# LurkerNanov12.net
KiCad netlist of a schematic drawn in EAGLE
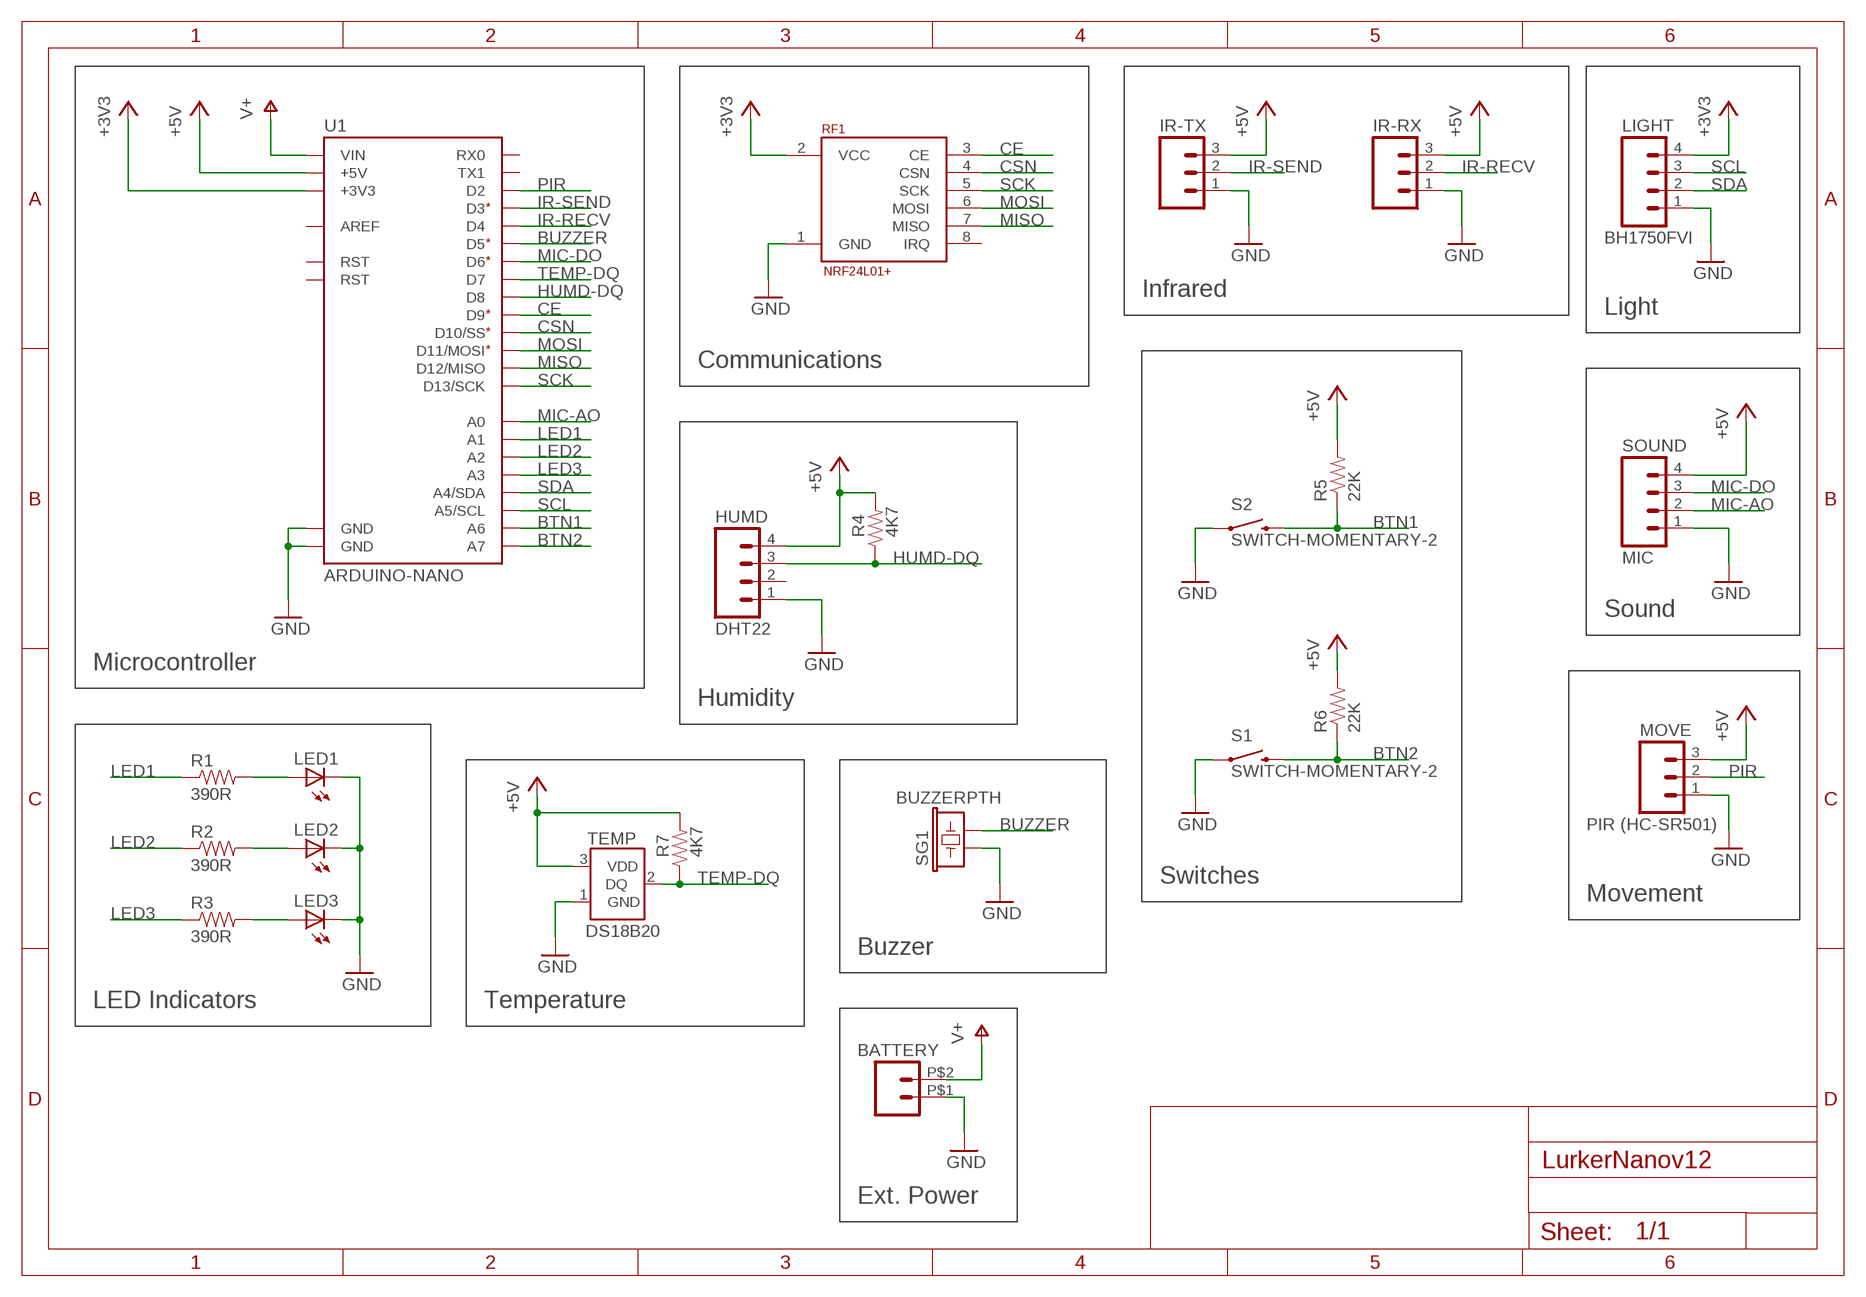
[diagram p0: schematic, sheet 1, part 1 of 2]
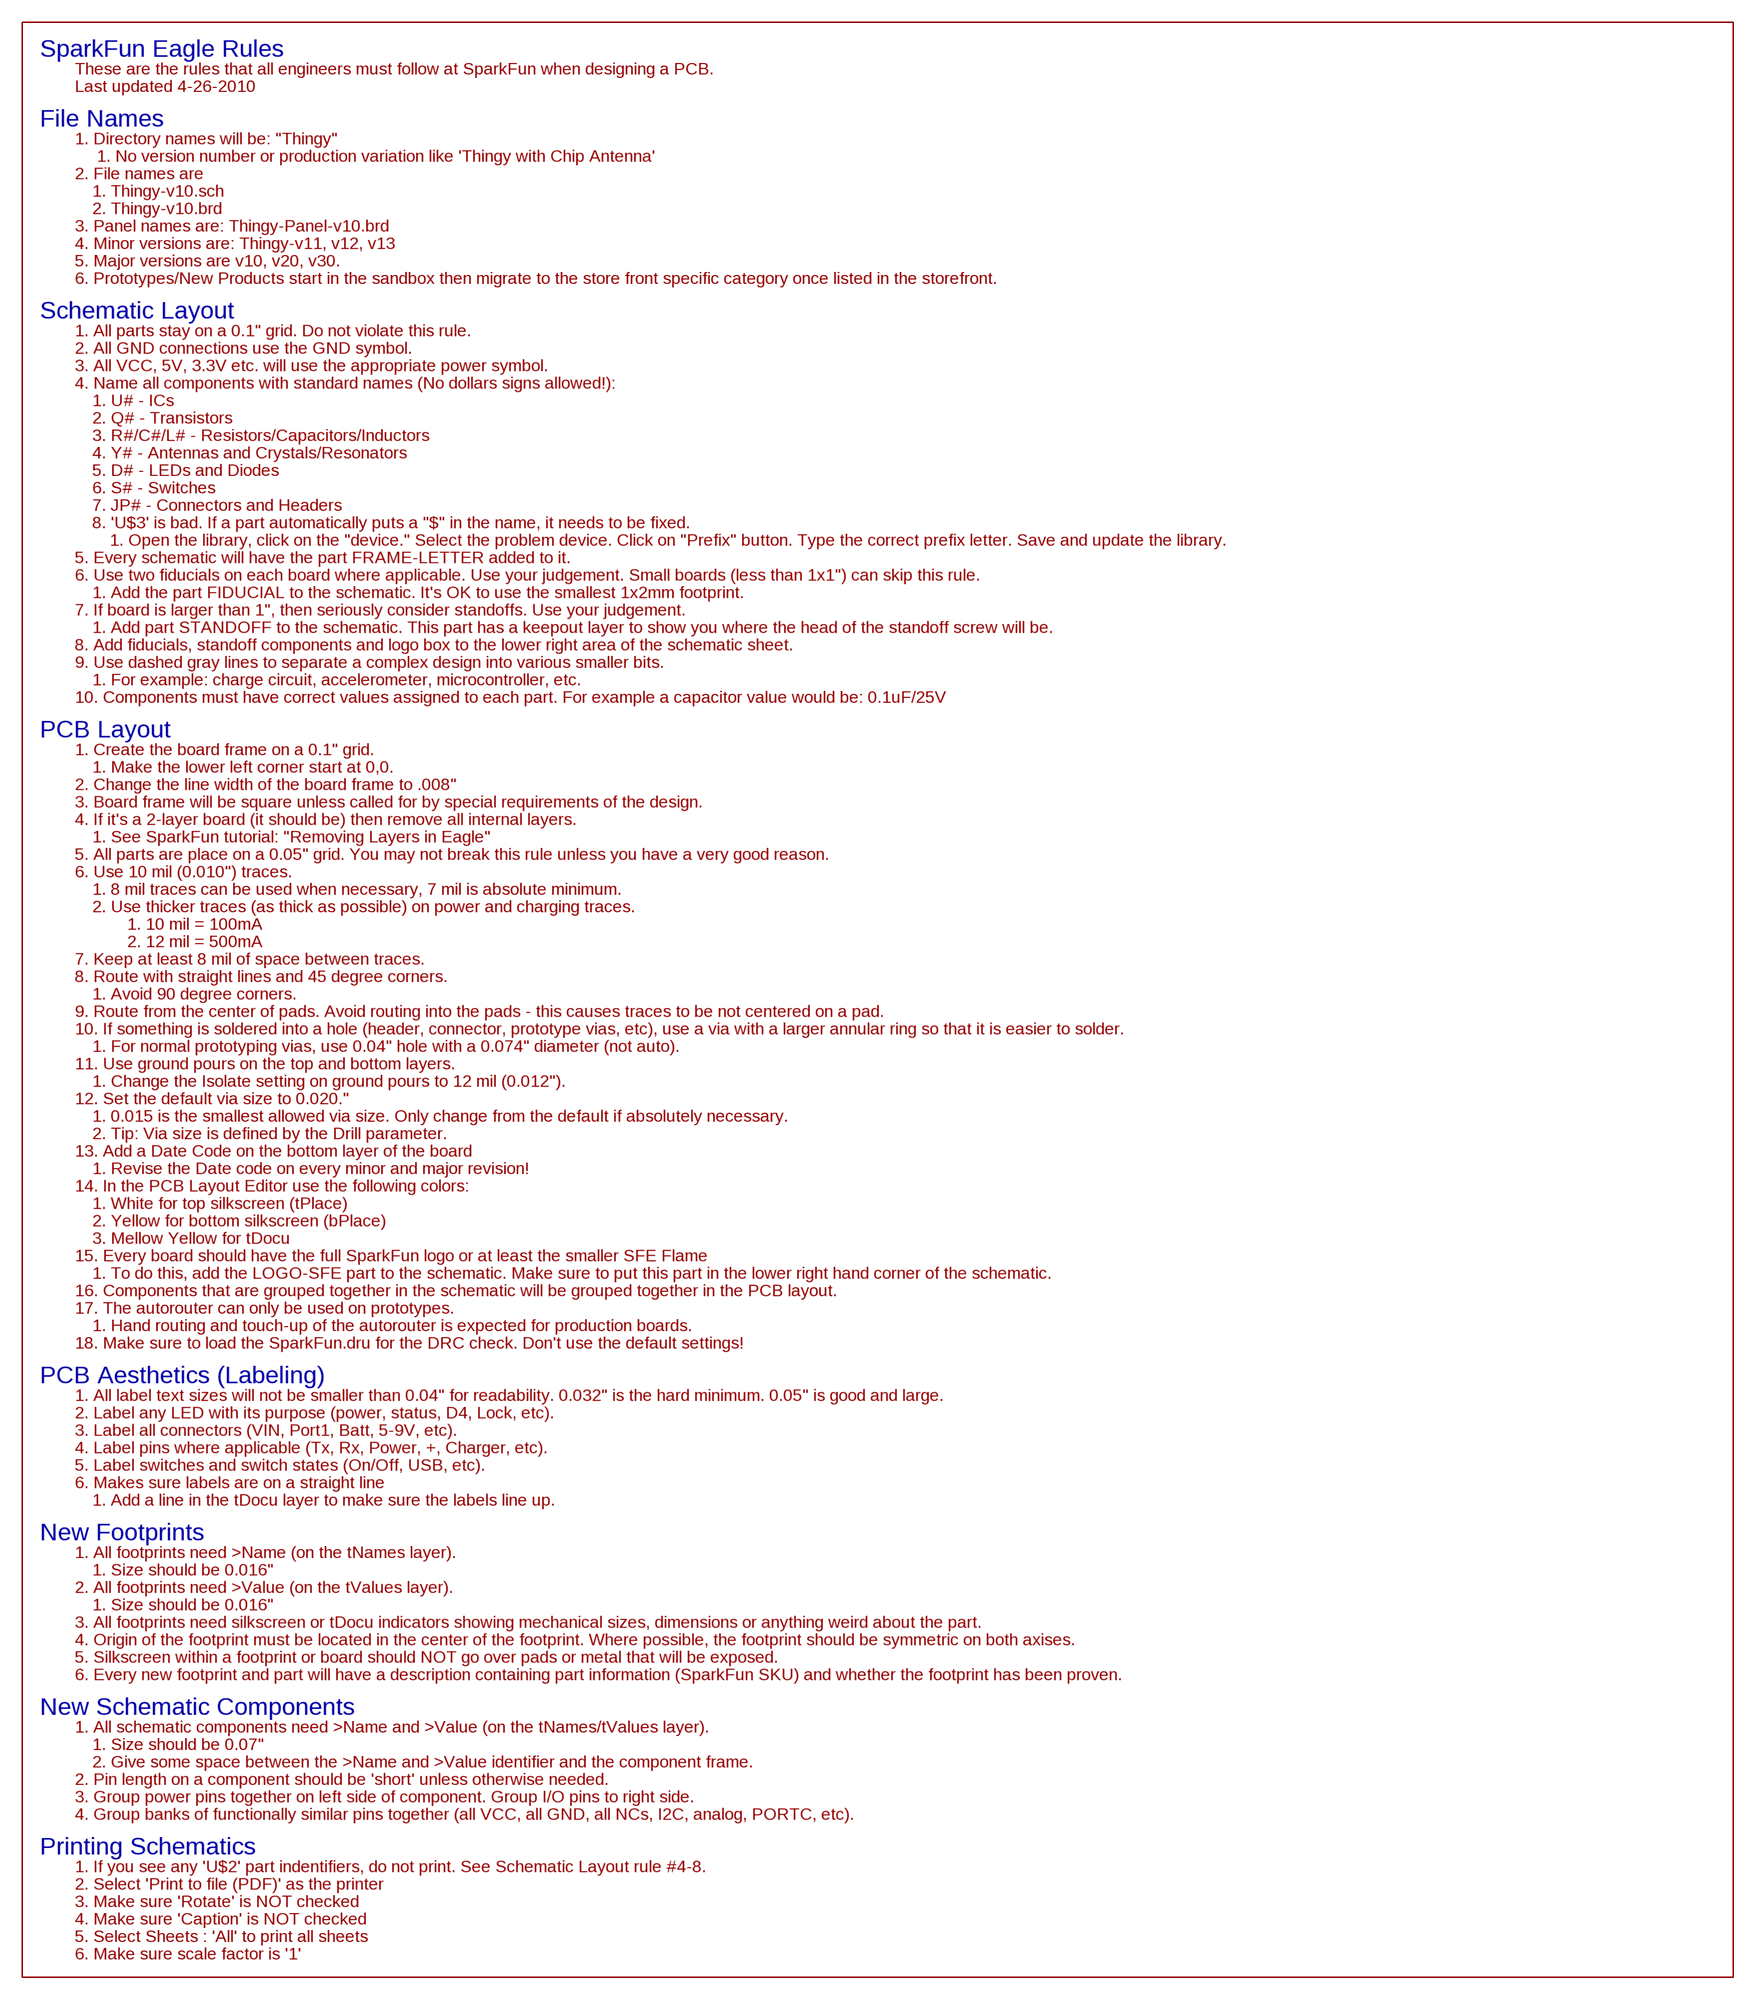
[diagram p1: schematic, sheet 1, part 2 of 2]

(export (version "E")
  (design (tool "Eeschema 10.0.6"))
  (components
    (comp (ref "BATTERY")
      (value "M02PTH2")
      (footprint "eagle-import:1X02_BIG")
      (libsource (lib "eagle-import") (part "M02PTH2"))
    )
    (comp (ref "HUMD")
      (value "DHT22")
      (footprint "eagle-import:1X04")
      (libsource (lib "eagle-import") (part "M04PTH"))
    )
    (comp (ref "IR-RX")
      (value "M03PTH")
      (footprint "eagle-import:1X03")
      (libsource (lib "eagle-import") (part "M03PTH"))
    )
    (comp (ref "IR-TX")
      (value "M03PTH")
      (footprint "eagle-import:1X03")
      (libsource (lib "eagle-import") (part "M03PTH"))
    )
    (comp (ref "LED1")
      (value "LED1206")
      (footprint "eagle-import:LED-1206")
      (libsource (lib "eagle-import") (part "LED1206"))
    )
    (comp (ref "LED2")
      (value "LED1206")
      (footprint "eagle-import:LED-1206")
      (libsource (lib "eagle-import") (part "LED1206"))
    )
    (comp (ref "LED3")
      (value "LED1206")
      (footprint "eagle-import:LED-1206")
      (libsource (lib "eagle-import") (part "LED1206"))
    )
    (comp (ref "LIGHT")
      (value "BH1750FVI")
      (footprint "eagle-import:1X04")
      (libsource (lib "eagle-import") (part "M04PTH"))
    )
    (comp (ref "MOVE")
      (value "PIR (HC-SR501)")
      (footprint "eagle-import:1X03")
      (libsource (lib "eagle-import") (part "M03PTH"))
    )
    (comp (ref "R1")
      (value "390R")
      (footprint "eagle-import:1206")
      (libsource (lib "eagle-import") (part "RESISTOR1206"))
    )
    (comp (ref "R2")
      (value "390R")
      (footprint "eagle-import:1206")
      (libsource (lib "eagle-import") (part "RESISTOR1206"))
    )
    (comp (ref "R3")
      (value "390R")
      (footprint "eagle-import:1206")
      (libsource (lib "eagle-import") (part "RESISTOR1206"))
    )
    (comp (ref "R4")
      (value "4K7")
      (footprint "eagle-import:1206")
      (libsource (lib "eagle-import") (part "RESISTOR1206"))
    )
    (comp (ref "R5")
      (value "22K")
      (footprint "eagle-import:1206")
      (libsource (lib "eagle-import") (part "RESISTOR1206"))
    )
    (comp (ref "R6")
      (value "22K")
      (footprint "eagle-import:1206")
      (libsource (lib "eagle-import") (part "RESISTOR1206"))
    )
    (comp (ref "R7")
      (value "4K7")
      (footprint "eagle-import:1206")
      (libsource (lib "eagle-import") (part "RESISTOR1206"))
    )
    (comp (ref "RF1")
      (value "NRF24L01+")
      (footprint "eagle-import:NRF24L01+-HEADER")
      (libsource (lib "eagle-import") (part "NRF24L01+"))
    )
    (comp (ref "S1")
      (value "SWITCH-MOMENTARY-2")
      (footprint "eagle-import:TACTILE_SWITCH_TALL")
      (libsource (lib "eagle-import") (part "SWITCH-MOMENTARY-2"))
    )
    (comp (ref "S2")
      (value "SWITCH-MOMENTARY-2")
      (footprint "eagle-import:TACTILE_SWITCH_TALL")
      (libsource (lib "eagle-import") (part "SWITCH-MOMENTARY-2"))
    )
    (comp (ref "SG1")
      (value "BUZZERPTH")
      (footprint "eagle-import:BUZZER-12MM")
      (libsource (lib "eagle-import") (part "BUZZERPTH"))
    )
    (comp (ref "SOUND")
      (value "MIC")
      (footprint "eagle-import:1X04")
      (libsource (lib "eagle-import") (part "M04PTH"))
    )
    (comp (ref "TEMP")
      (value "DS18B20")
      (footprint "eagle-import:TO-92-AMMO")
      (libsource (lib "eagle-import") (part "DS18B20"))
    )
    (comp (ref "U1")
      (value "ARDUINO-NANO")
      (footprint "eagle-import:NANO-SHIELD")
      (libsource (lib "eagle-import") (part "ARDUINO-NANO"))
    )
  )
  (nets
    (net (code "1") (name "+3V3") (class "Default")
      (node (ref "LIGHT") (pin "4") (pinfunction "4_4") (pintype "passive"))
      (node (ref "RF1") (pin "2") (pinfunction "VCC_2") (pintype "power_in"))
      (node (ref "U1") (pin "3V3") (pinfunction "+3V3_3V3") (pintype "power_in"))
    )
    (net (code "2") (name "+5V") (class "Default")
      (node (ref "HUMD") (pin "4") (pinfunction "4_4") (pintype "passive"))
      (node (ref "IR-RX") (pin "3") (pinfunction "3_3") (pintype "passive"))
      (node (ref "IR-TX") (pin "3") (pinfunction "3_3") (pintype "passive"))
      (node (ref "MOVE") (pin "3") (pinfunction "3_3") (pintype "passive"))
      (node (ref "R4") (pin "2") (pinfunction "2_2") (pintype "passive"))
      (node (ref "R5") (pin "2") (pinfunction "2_2") (pintype "passive"))
      (node (ref "R6") (pin "2") (pinfunction "2_2") (pintype "passive"))
      (node (ref "R7") (pin "2") (pinfunction "2_2") (pintype "passive"))
      (node (ref "SOUND") (pin "4") (pinfunction "4_4") (pintype "passive"))
      (node (ref "TEMP") (pin "3") (pinfunction "VDD_3") (pintype "power_in"))
      (node (ref "U1") (pin "5V") (pinfunction "+5V_5V") (pintype "power_in"))
    )
    (net (code "3") (name "/BTN1") (class "Default")
      (node (ref "R5") (pin "1") (pinfunction "1_1") (pintype "passive"))
      (node (ref "S2") (pin "B2") (pinfunction "2_B2") (pintype "passive"))
      (node (ref "U1") (pin "A6") (pinfunction "A6_A6") (pintype "bidirectional"))
    )
    (net (code "4") (name "/BTN2") (class "Default")
      (node (ref "R6") (pin "1") (pinfunction "1_1") (pintype "passive"))
      (node (ref "S1") (pin "B2") (pinfunction "2_B2") (pintype "passive"))
      (node (ref "U1") (pin "A7") (pinfunction "A7_A7") (pintype "bidirectional"))
    )
    (net (code "5") (name "/BUZZER") (class "Default")
      (node (ref "SG1") (pin "-") (pinfunction "2_-") (pintype "passive"))
      (node (ref "U1") (pin "D5") (pinfunction "D5_D5") (pintype "bidirectional"))
    )
    (net (code "6") (name "/CE") (class "Default")
      (node (ref "RF1") (pin "3") (pinfunction "CE_3") (pintype "bidirectional"))
      (node (ref "U1") (pin "D9") (pinfunction "D9_D9") (pintype "bidirectional"))
    )
    (net (code "7") (name "/CSN") (class "Default")
      (node (ref "RF1") (pin "4") (pinfunction "CSN_4") (pintype "bidirectional"))
      (node (ref "U1") (pin "D10") (pinfunction "D10/SS_D10") (pintype "bidirectional"))
    )
    (net (code "8") (name "/HUMD-DQ") (class "Default")
      (node (ref "HUMD") (pin "3") (pinfunction "3_3") (pintype "passive"))
      (node (ref "R4") (pin "1") (pinfunction "1_1") (pintype "passive"))
      (node (ref "U1") (pin "D8") (pinfunction "D8_D8") (pintype "bidirectional"))
    )
    (net (code "9") (name "/IR-RECV") (class "Default")
      (node (ref "IR-RX") (pin "2") (pinfunction "2_2") (pintype "passive"))
      (node (ref "U1") (pin "D4") (pinfunction "D4_D4") (pintype "bidirectional"))
    )
    (net (code "10") (name "/IR-SEND") (class "Default")
      (node (ref "IR-TX") (pin "2") (pinfunction "2_2") (pintype "passive"))
      (node (ref "U1") (pin "D3") (pinfunction "D3_D3") (pintype "bidirectional"))
    )
    (net (code "11") (name "/LED1") (class "Default")
      (node (ref "R1") (pin "1") (pinfunction "1_1") (pintype "passive"))
      (node (ref "U1") (pin "A1") (pinfunction "A1_A1") (pintype "bidirectional"))
    )
    (net (code "12") (name "/LED2") (class "Default")
      (node (ref "R2") (pin "1") (pinfunction "1_1") (pintype "passive"))
      (node (ref "U1") (pin "A2") (pinfunction "A2_A2") (pintype "bidirectional"))
    )
    (net (code "13") (name "/LED3") (class "Default")
      (node (ref "R3") (pin "1") (pinfunction "1_1") (pintype "passive"))
      (node (ref "U1") (pin "A3") (pinfunction "A3_A3") (pintype "bidirectional"))
    )
    (net (code "14") (name "/MIC-AO") (class "Default")
      (node (ref "SOUND") (pin "2") (pinfunction "2_2") (pintype "passive"))
      (node (ref "U1") (pin "A0") (pinfunction "A0_A0") (pintype "bidirectional"))
    )
    (net (code "15") (name "/MIC-DO") (class "Default")
      (node (ref "SOUND") (pin "3") (pinfunction "3_3") (pintype "passive"))
      (node (ref "U1") (pin "D6") (pinfunction "D6_D6") (pintype "bidirectional"))
    )
    (net (code "16") (name "/MISO") (class "Default")
      (node (ref "RF1") (pin "7") (pinfunction "MISO_7") (pintype "bidirectional"))
      (node (ref "U1") (pin "D12") (pinfunction "D12/MISO_D12") (pintype "bidirectional"))
    )
    (net (code "17") (name "/MOSI") (class "Default")
      (node (ref "RF1") (pin "6") (pinfunction "MOSI_6") (pintype "bidirectional"))
      (node (ref "U1") (pin "D11") (pinfunction "D11/MOSI_D11") (pintype "bidirectional"))
    )
    (net (code "18") (name "/PIR") (class "Default")
      (node (ref "MOVE") (pin "2") (pinfunction "2_2") (pintype "passive"))
      (node (ref "U1") (pin "D2") (pinfunction "D2_D2") (pintype "bidirectional"))
    )
    (net (code "19") (name "/SCK") (class "Default")
      (node (ref "RF1") (pin "5") (pinfunction "SCK_5") (pintype "bidirectional"))
      (node (ref "U1") (pin "D13") (pinfunction "D13/SCK_D13") (pintype "bidirectional"))
    )
    (net (code "20") (name "/SCL") (class "Default")
      (node (ref "LIGHT") (pin "3") (pinfunction "3_3") (pintype "passive"))
      (node (ref "U1") (pin "A5") (pinfunction "A5/SCL_A5") (pintype "bidirectional"))
    )
    (net (code "21") (name "/SDA") (class "Default")
      (node (ref "LIGHT") (pin "2") (pinfunction "2_2") (pintype "passive"))
      (node (ref "U1") (pin "A4") (pinfunction "A4/SDA_A4") (pintype "bidirectional"))
    )
    (net (code "22") (name "/TEMP-DQ") (class "Default")
      (node (ref "R7") (pin "1") (pinfunction "1_1") (pintype "passive"))
      (node (ref "TEMP") (pin "2") (pinfunction "DQ_2") (pintype "bidirectional"))
      (node (ref "U1") (pin "D7") (pinfunction "D7_D7") (pintype "bidirectional"))
    )
    (net (code "23") (name "GND") (class "Default")
      (node (ref "BATTERY") (pin "P$1") (pinfunction "1_P$1") (pintype "passive"))
      (node (ref "HUMD") (pin "1") (pinfunction "1_1") (pintype "passive"))
      (node (ref "IR-RX") (pin "1") (pinfunction "1_1") (pintype "passive"))
      (node (ref "IR-TX") (pin "1") (pinfunction "1_1") (pintype "passive"))
      (node (ref "LED1") (pin "C") (pinfunction "C_C") (pintype "passive"))
      (node (ref "LED2") (pin "C") (pinfunction "C_C") (pintype "passive"))
      (node (ref "LED3") (pin "C") (pinfunction "C_C") (pintype "passive"))
      (node (ref "LIGHT") (pin "1") (pinfunction "1_1") (pintype "passive"))
      (node (ref "MOVE") (pin "1") (pinfunction "1_1") (pintype "passive"))
      (node (ref "RF1") (pin "1") (pinfunction "GND_1") (pintype "power_in"))
      (node (ref "S1") (pin "A2") (pinfunction "1_A2") (pintype "passive"))
      (node (ref "S2") (pin "A2") (pinfunction "1_A2") (pintype "passive"))
      (node (ref "SG1") (pin "+") (pinfunction "1_+") (pintype "passive"))
      (node (ref "SOUND") (pin "1") (pinfunction "1_1") (pintype "passive"))
      (node (ref "TEMP") (pin "1") (pinfunction "GND_1") (pintype "power_in"))
      (node (ref "U1") (pin "GND@0") (pinfunction "GND_GND@0") (pintype "power_in"))
      (node (ref "U1") (pin "GND@1") (pinfunction "GND_GND@1") (pintype "power_in"))
    )
    (net (code "24") (name "Net-(LED1-PadA)") (class "Default")
      (node (ref "LED1") (pin "A") (pinfunction "A_A") (pintype "passive"))
      (node (ref "R1") (pin "2") (pinfunction "2_2") (pintype "passive"))
    )
    (net (code "25") (name "Net-(LED2-PadA)") (class "Default")
      (node (ref "LED2") (pin "A") (pinfunction "A_A") (pintype "passive"))
      (node (ref "R2") (pin "2") (pinfunction "2_2") (pintype "passive"))
    )
    (net (code "26") (name "Net-(LED3-PadA)") (class "Default")
      (node (ref "LED3") (pin "A") (pinfunction "A_A") (pintype "passive"))
      (node (ref "R3") (pin "2") (pinfunction "2_2") (pintype "passive"))
    )
    (net (code "27") (name "V+") (class "Default")
      (node (ref "BATTERY") (pin "P$2") (pinfunction "2_P$2") (pintype "passive"))
      (node (ref "U1") (pin "VIN") (pinfunction "VIN_VIN") (pintype "power_in"))
    )
    (net (code "28") (name "unconnected-(HUMD-Pad2)") (class "Default")
      (node (ref "HUMD") (pin "2") (pinfunction "2_2") (pintype "passive"))
    )
    (net (code "29") (name "unconnected-(RF1-IRQ-Pad8)") (class "Default")
      (node (ref "RF1") (pin "8") (pinfunction "IRQ_8") (pintype "bidirectional"))
    )
    (net (code "30") (name "unconnected-(U1-AREF-PadREF)") (class "Default")
      (node (ref "U1") (pin "REF") (pinfunction "AREF_REF") (pintype "output"))
    )
    (net (code "31") (name "unconnected-(U1-PadRST)") (class "Default")
      (node (ref "U1") (pin "RST") (pinfunction "RST_RST") (pintype "bidirectional"))
    )
    (net (code "32") (name "unconnected-(U1-RST-PadRST@0)") (class "Default")
      (node (ref "U1") (pin "RST@0") (pinfunction "RST_RST@0") (pintype "bidirectional"))
    )
    (net (code "33") (name "unconnected-(U1-RX0-PadRX)") (class "Default")
      (node (ref "U1") (pin "RX") (pinfunction "RX0_RX") (pintype "bidirectional"))
    )
    (net (code "34") (name "unconnected-(U1-TX1-PadTX)") (class "Default")
      (node (ref "U1") (pin "TX") (pinfunction "TX1_TX") (pintype "bidirectional"))
    )
  )
)
